# Schematic.net
KiCad netlist of a schematic drawn in Altium Designer
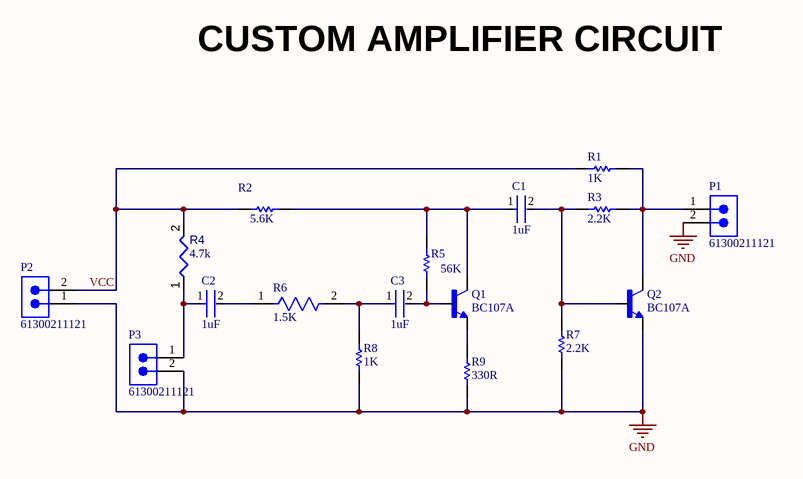
[diagram p0: Schematic.SchDoc]

(export (version "E")
  (design (tool "Eeschema 10.0.6"))
  (components
    (comp (ref "C1")
      (value "1uF")
      (footprint "FP-1206-L_3_2_0_2-W_1_6_0-IPC_A")
      (description "General Purpose Ceramic Capacitor, 1206, 1uF, 10%, X7R, 15%, 25V")
      (fields (field (name "TOLERANCE") "10%") (field (name "VOLTAGE") "25V"))
      (libsource (lib "Altium Content Vault") (part "b4654b650e69147ec39a6b967a45e02"))
    )
    (comp (ref "C2")
      (value "1uF")
      (footprint "FP-1206-L_3_2_0_2-W_1_6_0-IPC_A")
      (description "General Purpose Ceramic Capacitor, 1206, 1uF, 10%, X7R, 15%, 25V")
      (fields (field (name "TOLERANCE") "10%") (field (name "VOLTAGE") "25V"))
      (libsource (lib "Altium Content Vault") (part "b4654b650e69147ec39a6b967a45e02"))
    )
    (comp (ref "C3")
      (value "1uF")
      (footprint "FP-1206-L_3_2_0_2-W_1_6_0-IPC_A")
      (description "General Purpose Ceramic Capacitor, 1206, 1uF, 10%, X7R, 15%, 25V")
      (fields (field (name "TOLERANCE") "10%") (field (name "VOLTAGE") "25V"))
      (libsource (lib "Altium Content Vault") (part "b4654b650e69147ec39a6b967a45e02"))
    )
    (comp (ref "P1")
      (value "61300211121")
      (footprint "61300211121")
      (libsource (lib "Altium Content Vault") (part "Header_Male_1R_02P"))
    )
    (comp (ref "P2")
      (value "61300211121")
      (footprint "61300211121")
      (libsource (lib "Altium Content Vault") (part "Header_Male_1R_02P"))
    )
    (comp (ref "P3")
      (value "61300211121")
      (footprint "61300211121")
      (libsource (lib "Altium Content Vault") (part "Header_Male_1R_02P"))
    )
    (comp (ref "Q1")
      (value "BC107A")
      (footprint "TO18")
      (description "Bipolar (BJT) Transistor")
      (fields (field (name "MF") "Multicomp"))
      (libsource (lib "BC107A") (part "BC107A"))
    )
    (comp (ref "Q2")
      (value "BC107A")
      (footprint "TO18")
      (description "Bipolar (BJT) Transistor")
      (fields (field (name "MF") "Multicomp"))
      (libsource (lib "BC107A") (part "BC107A"))
    )
    (comp (ref "R1")
      (value "1K")
      (footprint "RESC3116X65X40ML10T20")
      (description "Chip Resistor, 1 KOhm, +/- 1%, 0.25 W, -55 to 155 degC, 1206 (3216 Metric), RoHS, Tape and Reel")
      (fields (field (name "TOLERANCE") "1%") (field (name "MANUFACTURER") "Yageo"))
      (libsource (lib "Altium Content Vault") (part "RES-2"))
    )
    (comp (ref "R2")
      (value "5.6K")
      (footprint "RESC3216X60X45LL10T20")
      (fields (field (name "MANUFACTURER") "Vishay Dale") (field (name "PART NUMBER") "CRCW12065K60FKEA"))
      (libsource (lib "Altium Content Vault") (part "RES"))
    )
    (comp (ref "R3")
      (value "2.2K")
      (footprint "RESC3116X65X40ML10T20")
      (description "Chip Resistor, 2.2 KOhm, +/- 1%, 250 mW, -55 to 155 degC, 1206 (3216 Metric), RoHS, Tape and Reel")
      (fields (field (name "MANUFACTURER") "Yageo") (field (name "TOLERANCE") "1%"))
      (libsource (lib "Altium Content Vault") (part "RES-2"))
    )
    (comp (ref "R4")
      (value "4.7k")
      (footprint "RESC3116X70X50ML13T20")
      (description "Chip Resistor, 4.7 KOhm, +/- 1%, 0.25 W, -55 to 155 degC, 1206 (3216 Metric)")
      (fields (field (name "POWER") "250mW") (field (name "TOLERANCE") "1%"))
      (libsource (lib "Bannari Amman Institute of Technology") (part "RES-2"))
    )
    (comp (ref "R5")
      (value "56K")
      (footprint "RESC3216X60X45NL10T20")
      (fields (field (name "PART NUMBER") "CRCW120656K0JNEA") (field (name "MANUFACTURER") "Vishay Dale"))
      (libsource (lib "Altium Content Vault") (part "RES"))
    )
    (comp (ref "R6")
      (value "1.5K")
      (footprint "FP-CRCW1206-e3-IPC_C")
      (description "RES Thick Film, 1.5kΩ, 1%, 0.25W, 100ppm/°C, 1206")
      (fields (field (name "TOLERANCE") "1%"))
      (libsource (lib "Altium Content Vault") (part "1029c3af85768c4190bb7ad29bc67b5"))
    )
    (comp (ref "R7")
      (value "2.2K")
      (footprint "RESC3116X65X40ML10T20")
      (description "Chip Resistor, 2.2 KOhm, +/- 1%, 250 mW, -55 to 155 degC, 1206 (3216 Metric), RoHS, Tape and Reel")
      (fields (field (name "MANUFACTURER") "Yageo") (field (name "TOLERANCE") "1%"))
      (libsource (lib "Altium Content Vault") (part "RES-2"))
    )
    (comp (ref "R8")
      (value "1K")
      (footprint "RESC3116X65X40ML10T20")
      (description "Chip Resistor, 1 KOhm, +/- 1%, 0.25 W, -55 to 155 degC, 1206 (3216 Metric), RoHS, Tape and Reel")
      (fields (field (name "TOLERANCE") "1%") (field (name "MANUFACTURER") "Yageo"))
      (libsource (lib "Altium Content Vault") (part "RES-2"))
    )
    (comp (ref "R9")
      (value "330R")
      (footprint "RESC3216X70X50NL05T20")
      (fields (field (name "PART NUMBER") "ERJ8ENF3300V") (field (name "MANUFACTURER") "Panasonic"))
      (libsource (lib "Altium Content Vault") (part "RES"))
    )
  )
  (nets
    (net (code "1") (name "/VCC") (class "Default")
      (node (ref "P2") (pin "2") (pinfunction "2_2") (pintype "passive"))
      (node (ref "R1") (pin "2") (pinfunction "2_2") (pintype "passive"))
      (node (ref "R2") (pin "1") (pinfunction "1_1") (pintype "passive"))
      (node (ref "R4") (pin "2") (pinfunction "2_2") (pintype "passive"))
    )
    (net (code "2") (name "GND") (class "Default")
      (node (ref "P1") (pin "2") (pinfunction "2_2") (pintype "passive"))
      (node (ref "P2") (pin "1") (pinfunction "1_1") (pintype "passive"))
      (node (ref "P3") (pin "2") (pinfunction "2_2") (pintype "passive"))
      (node (ref "Q2") (pin "1") (pinfunction "E_1") (pintype "passive"))
      (node (ref "R7") (pin "1") (pinfunction "1_1") (pintype "passive"))
      (node (ref "R8") (pin "1") (pinfunction "1_1") (pintype "passive"))
      (node (ref "R9") (pin "1") (pinfunction "1_1") (pintype "passive"))
    )
    (net (code "3") (name "Net-(C2-Pad1)") (class "Default")
      (node (ref "C2") (pin "1") (pinfunction "1_1") (pintype "passive"))
      (node (ref "P3") (pin "1") (pinfunction "1_1") (pintype "passive"))
      (node (ref "R4") (pin "1") (pinfunction "1_1") (pintype "passive"))
    )
    (net (code "4") (name "Net-(C2-Pad2)") (class "Default")
      (node (ref "C2") (pin "2") (pinfunction "2_2") (pintype "passive"))
      (node (ref "R6") (pin "1") (pinfunction "1_1") (pintype "passive"))
    )
    (net (code "5") (name "Net-(C3-Pad1)") (class "Default")
      (node (ref "C3") (pin "1") (pinfunction "1_1") (pintype "passive"))
      (node (ref "R6") (pin "2") (pinfunction "2_2") (pintype "passive"))
      (node (ref "R8") (pin "2") (pinfunction "2_2") (pintype "passive"))
    )
    (net (code "6") (name "Net-(Q1-B)") (class "Default")
      (node (ref "C3") (pin "2") (pinfunction "2_2") (pintype "passive"))
      (node (ref "Q1") (pin "2") (pinfunction "B_2") (pintype "passive"))
      (node (ref "R5") (pin "1") (pinfunction "1_1") (pintype "passive"))
    )
    (net (code "7") (name "Net-(Q1-C)") (class "Default")
      (node (ref "C1") (pin "1") (pinfunction "1_1") (pintype "passive"))
      (node (ref "Q1") (pin "3") (pinfunction "C_3") (pintype "passive"))
      (node (ref "R2") (pin "2") (pinfunction "2_2") (pintype "passive"))
      (node (ref "R5") (pin "2") (pinfunction "2_2") (pintype "passive"))
    )
    (net (code "8") (name "Net-(Q1-E)") (class "Default")
      (node (ref "Q1") (pin "1") (pinfunction "E_1") (pintype "passive"))
      (node (ref "R9") (pin "2") (pinfunction "2_2") (pintype "passive"))
    )
    (net (code "9") (name "Net-(Q2-B)") (class "Default")
      (node (ref "C1") (pin "2") (pinfunction "2_2") (pintype "passive"))
      (node (ref "Q2") (pin "2") (pinfunction "B_2") (pintype "passive"))
      (node (ref "R3") (pin "1") (pinfunction "1_1") (pintype "passive"))
      (node (ref "R7") (pin "2") (pinfunction "2_2") (pintype "passive"))
    )
    (net (code "10") (name "Net-(Q2-C)") (class "Default")
      (node (ref "P1") (pin "1") (pinfunction "1_1") (pintype "passive"))
      (node (ref "Q2") (pin "3") (pinfunction "C_3") (pintype "passive"))
      (node (ref "R1") (pin "1") (pinfunction "1_1") (pintype "passive"))
      (node (ref "R3") (pin "2") (pinfunction "2_2") (pintype "passive"))
    )
  )
)
